# Down_Resistors.net
KiCad netlist of a schematic drawn in EAGLE
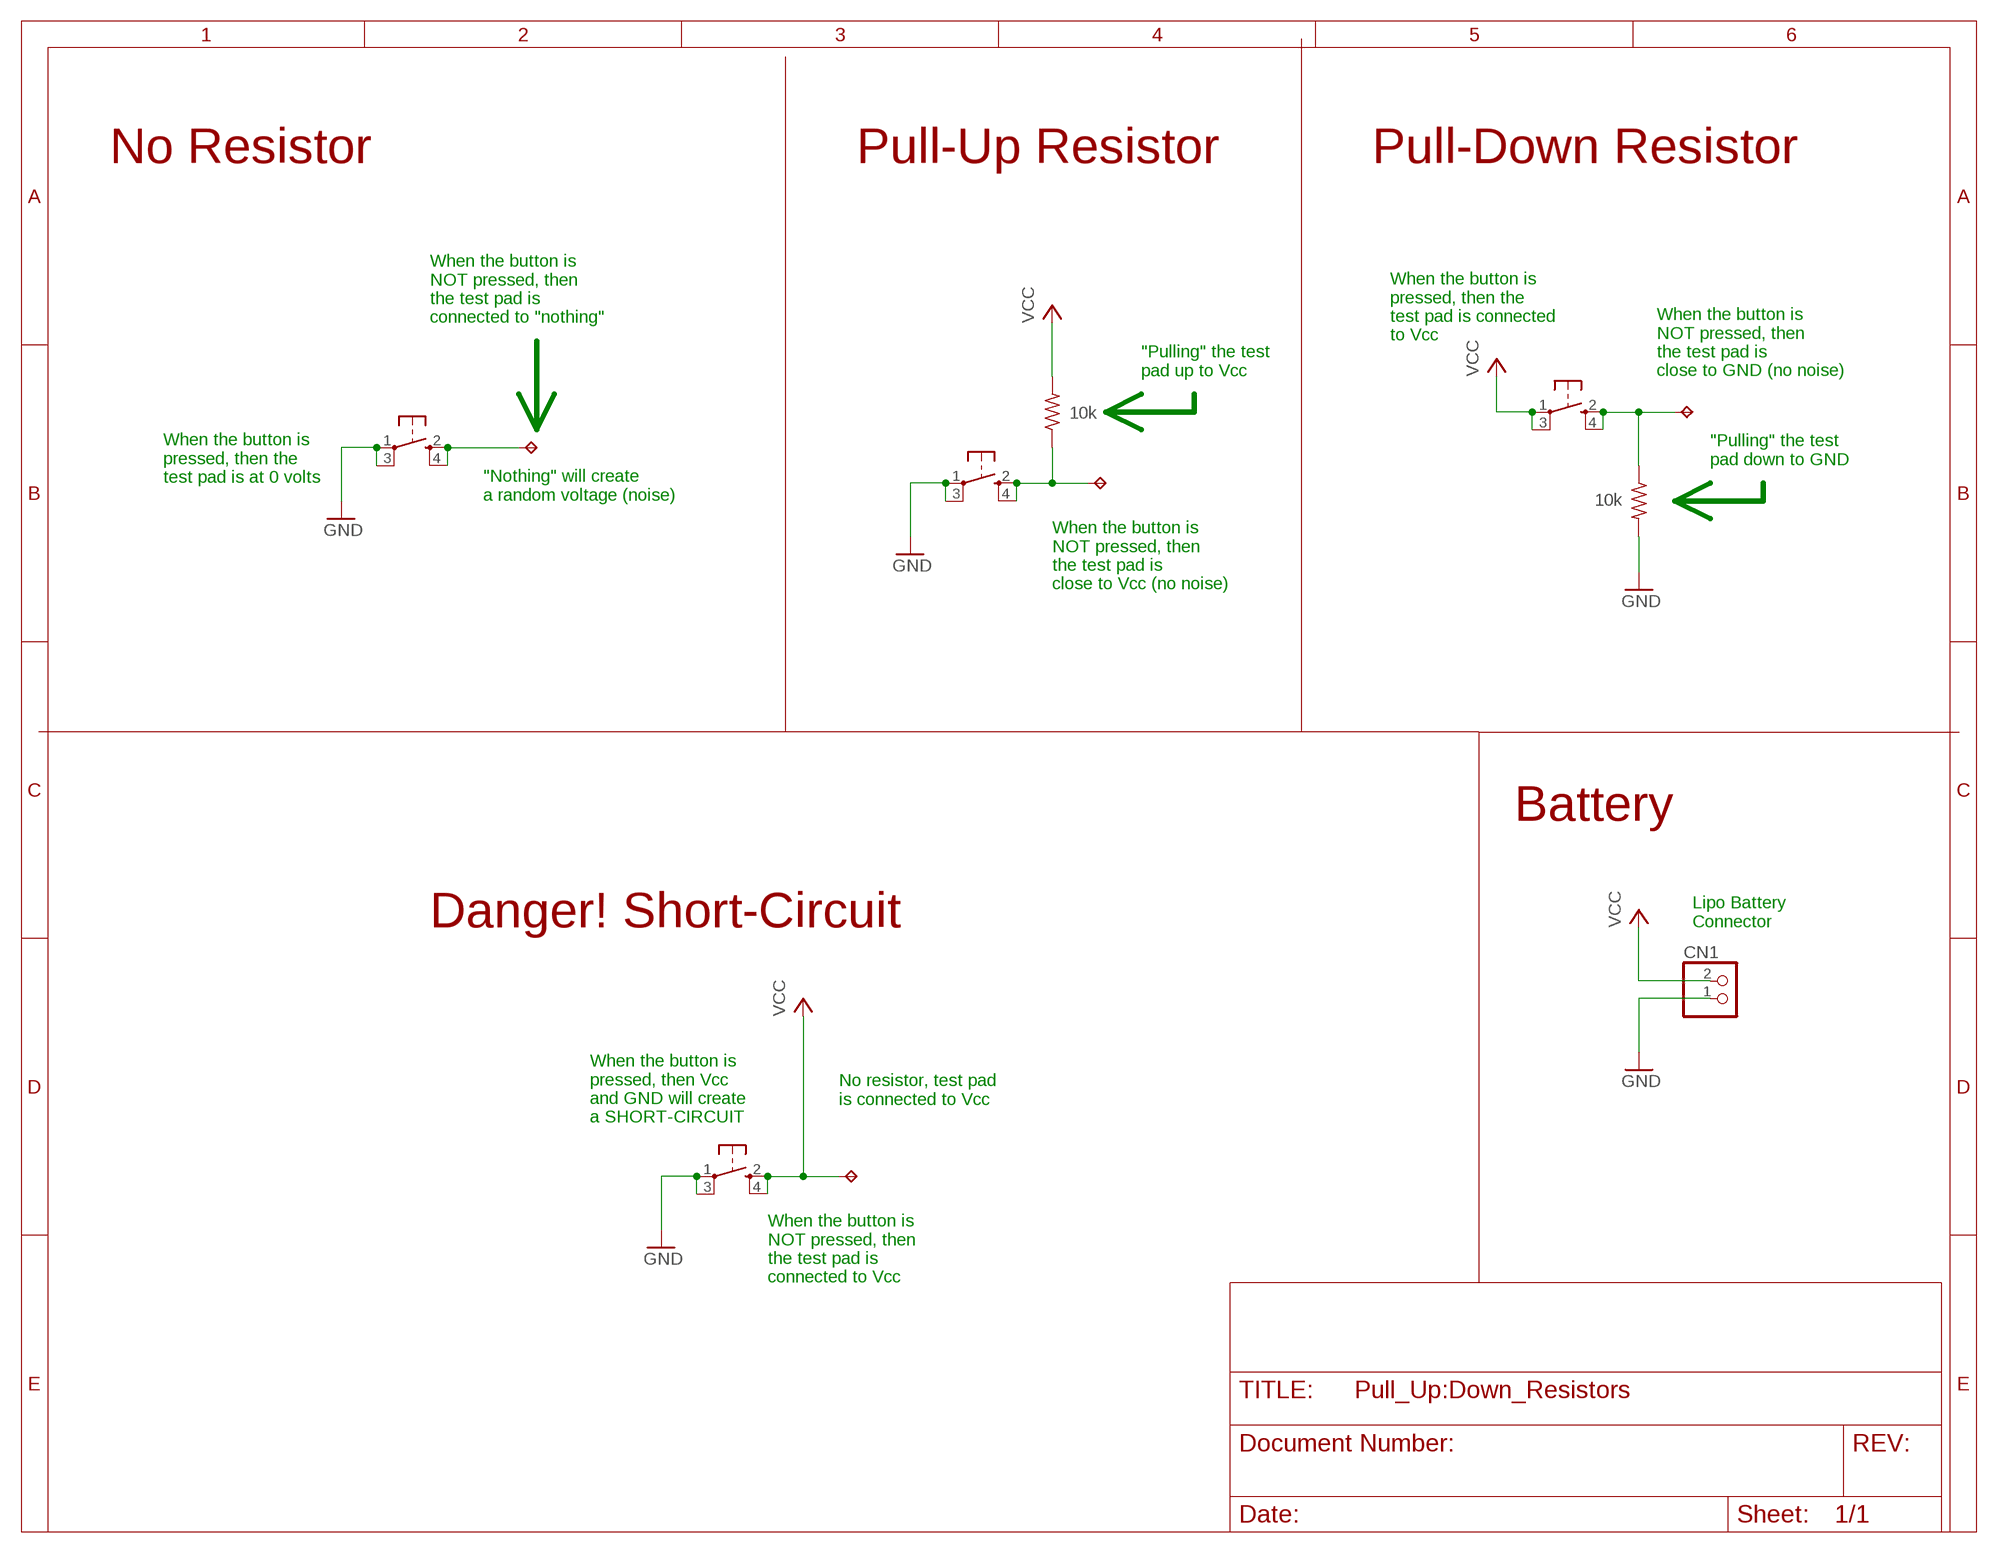
[diagram p0: schematic, sheet 1]

(export (version "E")
  (design (tool "Eeschema 10.0.6"))
  (components
    (comp (ref "CN1")
      (value "JST_2PIN-SMT-RA")
      (footprint "eagle-import:JST-PH-2-SMT-RA")
      (libsource (lib "eagle-import") (part "JST_2PIN-SMT-RA"))
    )
    (comp (ref "R1")
      (value "10k")
      (footprint "eagle-import:R0603")
      (libsource (lib "eagle-import") (part "R-US_R0603"))
    )
    (comp (ref "R2")
      (value "10k")
      (footprint "eagle-import:R0603")
      (libsource (lib "eagle-import") (part "R-US_R0603"))
    )
    (comp (ref "SW1")
      (value "SPST_TACT-KMR2")
      (footprint "eagle-import:KMR2")
      (libsource (lib "eagle-import") (part "SPST_TACT-KMR2"))
    )
    (comp (ref "SW2")
      (value "SPST_TACT-KMR2")
      (footprint "eagle-import:KMR2")
      (libsource (lib "eagle-import") (part "SPST_TACT-KMR2"))
    )
    (comp (ref "SW3")
      (value "SPST_TACT-KMR2")
      (footprint "eagle-import:KMR2")
      (libsource (lib "eagle-import") (part "SPST_TACT-KMR2"))
    )
    (comp (ref "SW4")
      (value "SPST_TACT-KMR2")
      (footprint "eagle-import:KMR2")
      (libsource (lib "eagle-import") (part "SPST_TACT-KMR2"))
    )
    (comp (ref "TP1")
      (value "TPTP20R")
      (footprint "eagle-import:TP20R")
      (libsource (lib "eagle-import") (part "TPTP20R"))
    )
    (comp (ref "TP2")
      (value "TPTP20R")
      (footprint "eagle-import:TP20R")
      (libsource (lib "eagle-import") (part "TPTP20R"))
    )
    (comp (ref "TP3")
      (value "TPTP20R")
      (footprint "eagle-import:TP20R")
      (libsource (lib "eagle-import") (part "TPTP20R"))
    )
    (comp (ref "TP4")
      (value "TPTP20R")
      (footprint "eagle-import:TP20R")
      (libsource (lib "eagle-import") (part "TPTP20R"))
    )
  )
  (nets
    (net (code "3") (name "GND") (class "Default")
      (node (ref "CN1") (pin "1") (pinfunction "2_1") (pintype "passive"))
      (node (ref "R2") (pin "2") (pinfunction "2_2") (pintype "passive"))
      (node (ref "SW1") (pin "1") (pinfunction "P_1") (pintype "passive"))
      (node (ref "SW1") (pin "3") (pinfunction "P1_3") (pintype "passive"))
      (node (ref "SW2") (pin "1") (pinfunction "P_1") (pintype "passive"))
      (node (ref "SW2") (pin "3") (pinfunction "P1_3") (pintype "passive"))
      (node (ref "SW3") (pin "1") (pinfunction "P_1") (pintype "passive"))
      (node (ref "SW3") (pin "3") (pinfunction "P1_3") (pintype "passive"))
    )
    (net (code "4") (name "Net-(SW1-S)") (class "Default")
      (node (ref "SW1") (pin "2") (pinfunction "S_2") (pintype "passive"))
      (node (ref "SW1") (pin "4") (pinfunction "S1_4") (pintype "passive"))
      (node (ref "TP1") (pin "TP") (pinfunction "TP_TP") (pintype "input"))
    )
    (net (code "5") (name "Net-(SW2-S)") (class "Default")
      (node (ref "R1") (pin "1") (pinfunction "1_1") (pintype "passive"))
      (node (ref "SW2") (pin "2") (pinfunction "S_2") (pintype "passive"))
      (node (ref "SW2") (pin "4") (pinfunction "S1_4") (pintype "passive"))
      (node (ref "TP2") (pin "TP") (pinfunction "TP_TP") (pintype "input"))
    )
    (net (code "6") (name "Net-(SW4-S)") (class "Default")
      (node (ref "R2") (pin "1") (pinfunction "1_1") (pintype "passive"))
      (node (ref "SW4") (pin "2") (pinfunction "S_2") (pintype "passive"))
      (node (ref "SW4") (pin "4") (pinfunction "S1_4") (pintype "passive"))
      (node (ref "TP4") (pin "TP") (pinfunction "TP_TP") (pintype "input"))
    )
    (net (code "7") (name "VCC") (class "Default")
      (node (ref "CN1") (pin "2") (pinfunction "1_2") (pintype "passive"))
      (node (ref "R1") (pin "2") (pinfunction "2_2") (pintype "passive"))
      (node (ref "SW3") (pin "2") (pinfunction "S_2") (pintype "passive"))
      (node (ref "SW3") (pin "4") (pinfunction "S1_4") (pintype "passive"))
      (node (ref "SW4") (pin "1") (pinfunction "P_1") (pintype "passive"))
      (node (ref "SW4") (pin "3") (pinfunction "P1_3") (pintype "passive"))
      (node (ref "TP3") (pin "TP") (pinfunction "TP_TP") (pintype "input"))
    )
  )
)
